# EasyEDA_Source.net
KiCad netlist of a schematic drawn in EasyEDA
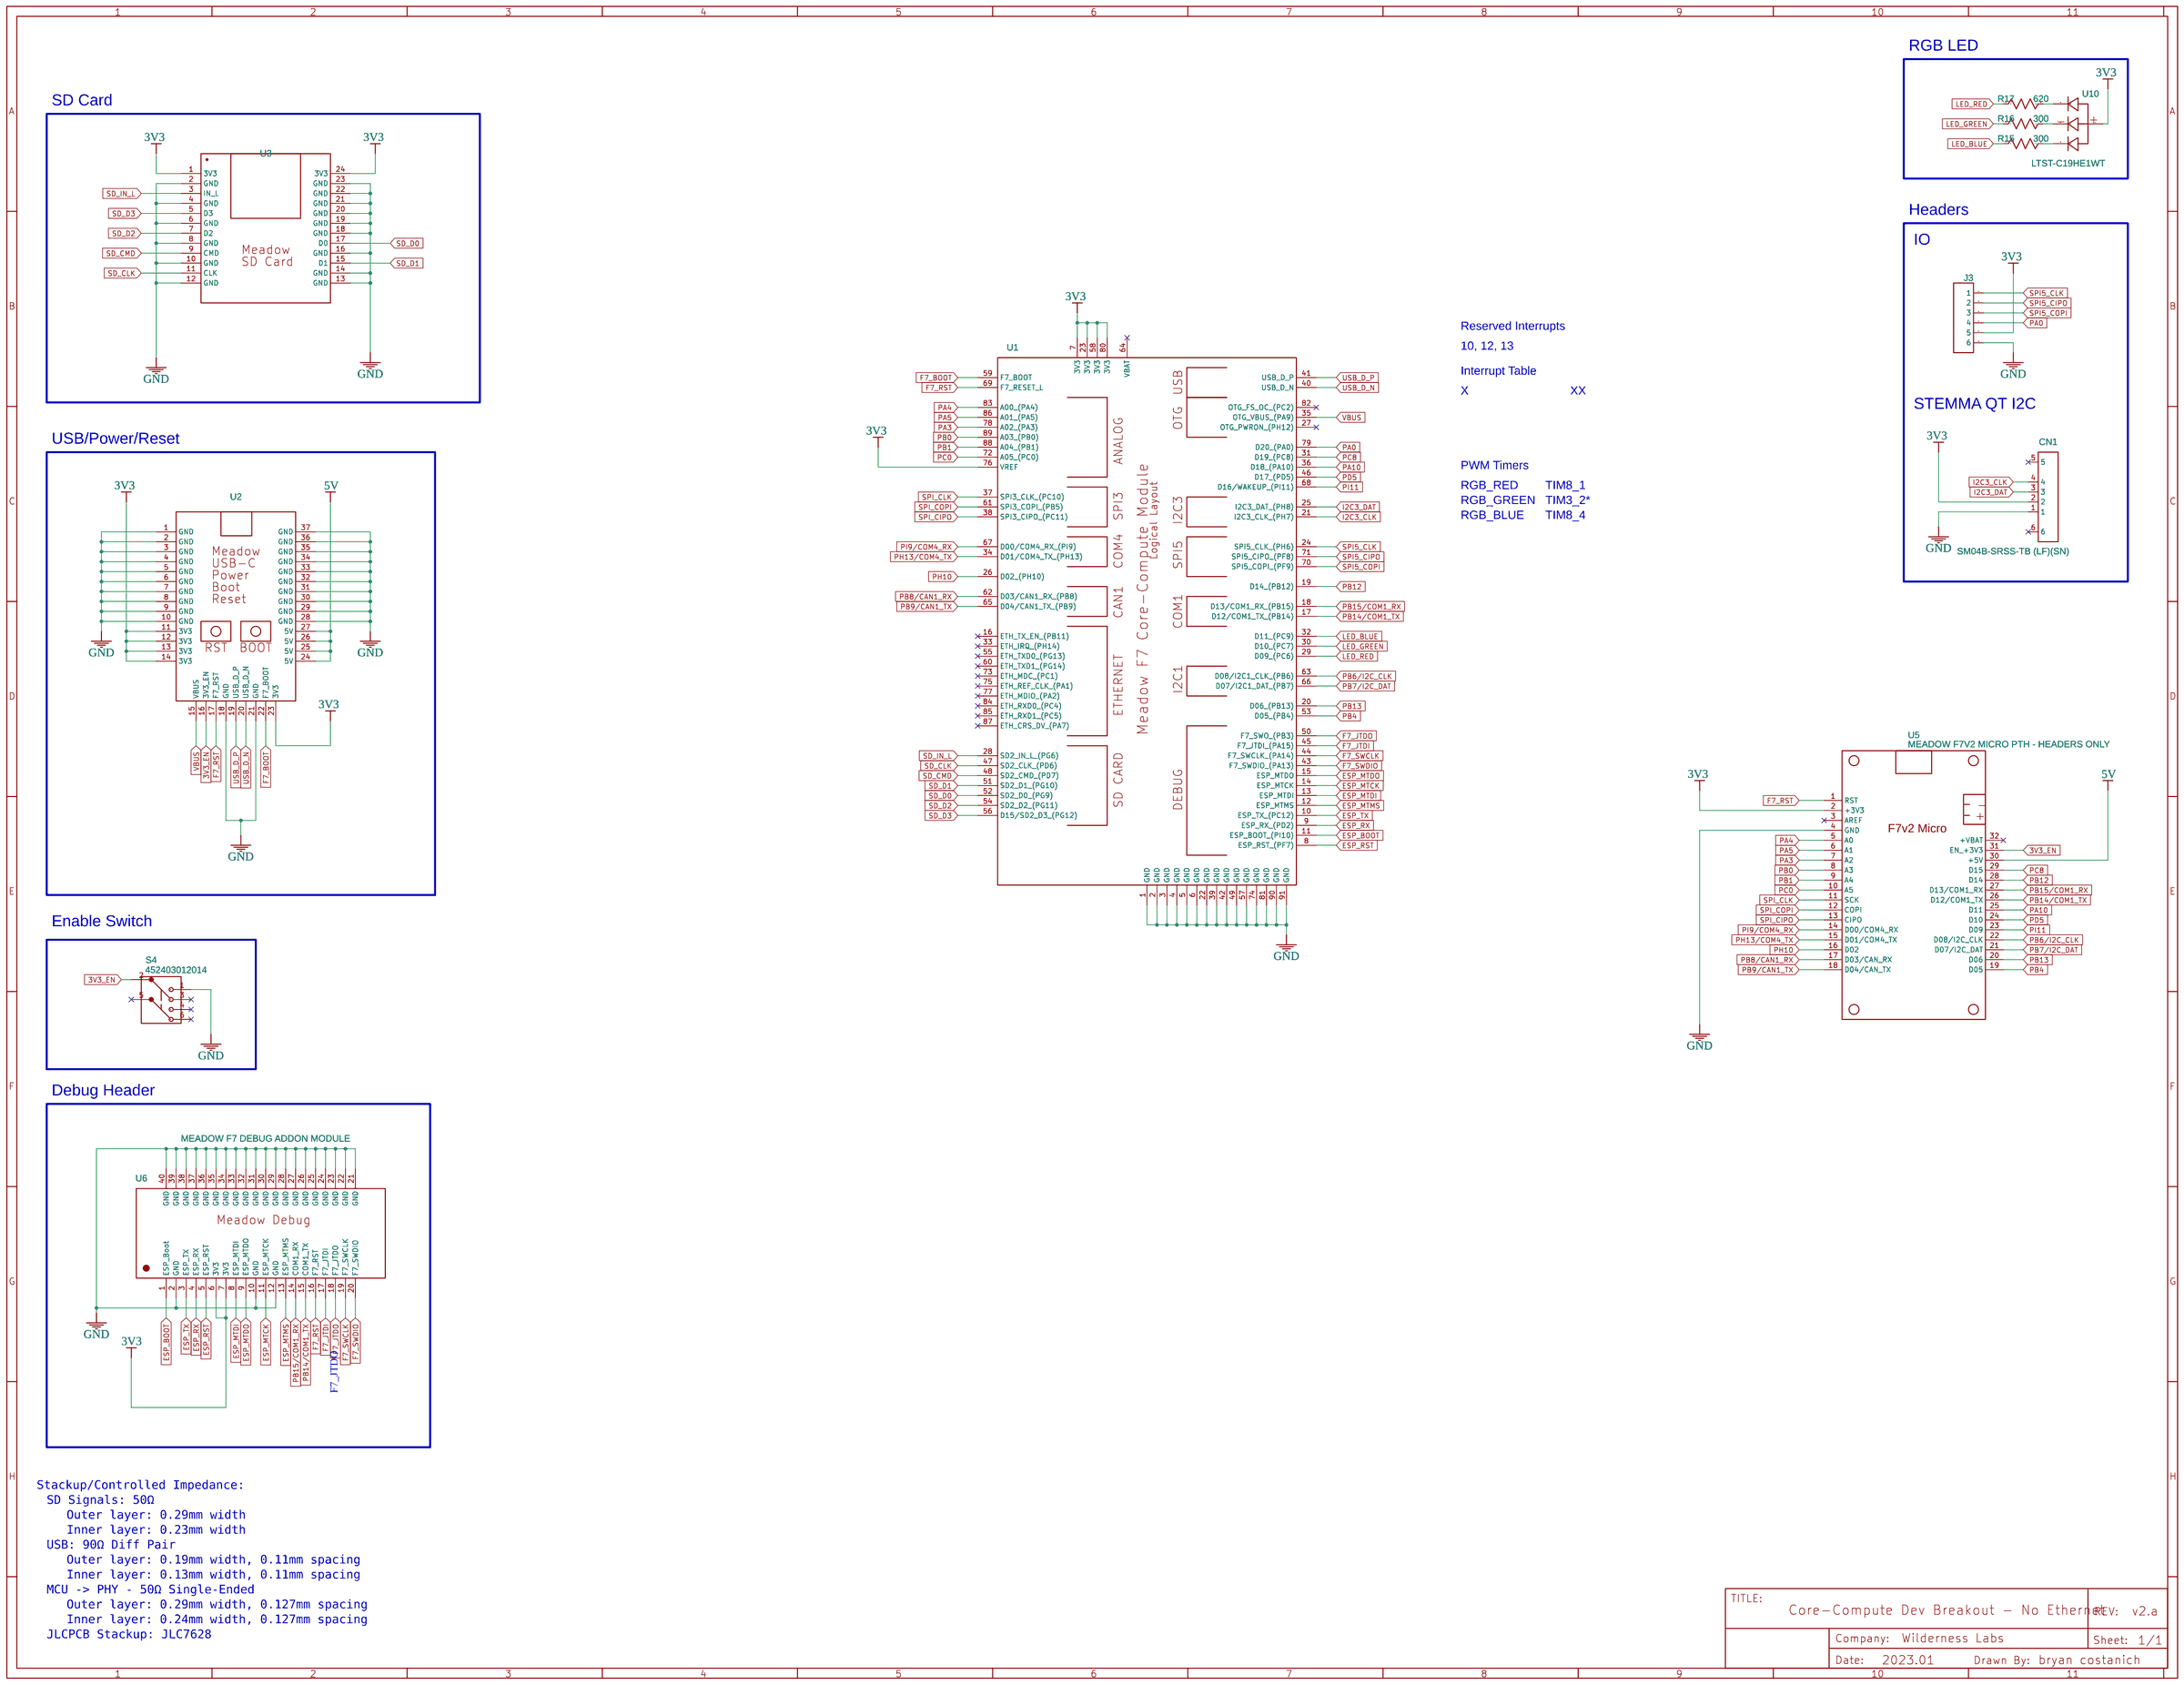
[diagram p0: schematic sheet]

(export (version "E")
  (design (tool "Eeschema 10.0.6"))
  (components
    (comp (ref "CN1")
      (value "SM04B-SRSS-TB (LF)(SN)")
      (fields (field (name "BOM_Supplier Part") "C160404"))
      (libsource (lib "") (part "SM04B-SRSS-TB (LF)(SN)"))
    )
    (comp (ref "J3")
      (value "HDR-M-2.54_1x6")
      (fields (field (name "BOM_Supplier Part") "C190819"))
      (libsource (lib "") (part "HDR-M-2.54_1x6"))
    )
    (comp (ref "R15")
      (value "300")
      (fields (field (name "BOM_Manufacturer Part") "RC0603FR-07300RL"))
      (libsource (lib "") (part "R_0603_US"))
    )
    (comp (ref "R16")
      (value "300")
      (fields (field (name "BOM_Manufacturer Part") "RC0603FR-07300RL"))
      (libsource (lib "") (part "R_0603_US"))
    )
    (comp (ref "R17")
      (value "620")
      (fields (field (name "BOM_Manufacturer Part") "RC0603FR-07620RL"))
      (libsource (lib "") (part "R_0603_US"))
    )
    (comp (ref "S4") (value "452403012014") (libsource (lib "") (part "452403012014")))
    (comp (ref "U1")
      (value "Meadow F7v2 Core-Compute Module - Logical")
      (libsource (lib "") (part "Meadow F7v2 Core-Compute Module - Logical"))
    )
    (comp (ref "U2")
      (value "Meadow Core-Compute USB-C, Power, Boot, and Reset Addon Module")
      (libsource (lib "") (part "Meadow Core-Compute USB-C, Power, Boot, and Reset Addon Module"))
    )
    (comp (ref "U3")
      (value "Meadow Core-Compute SD-Card Addon")
      (libsource (lib "") (part "Meadow Core-Compute SD-Card Addon"))
    )
    (comp (ref "U5")
      (value "MEADOW F7V2 MICRO PTH - HEADERS ONLY")
      (fields
        (field (name "BOM_Manufacturer Part") "MEDF7DEV")
        (field (name "BOM_Supplier Part") "977-MEADOWF7MICRO")
      )
      (libsource (lib "") (part "MEADOW F7V2 MICRO PTH - HEADERS ONLY"))
    )
    (comp (ref "U6")
      (value "MEADOW F7 DEBUG ADDON MODULE")
      (libsource (lib "") (part "MEADOW F7 DEBUG ADDON MODULE"))
    )
    (comp (ref "U10")
      (value "LTST-C19HE1WT")
      (fields
        (field (name "BOM_Manufacturer Part") "LTST-C19HE1WT-H")
        (field (name "BOM_Supplier Part") "C427425")
      )
      (libsource (lib "") (part "LTST-C19HE1WT-H"))
    )
  )
  (nets
    (net (code "1") (name "3V3") (class "Default")
      (node (ref "CN1") (pin "2") (pinfunction "2_2") (pintype "unspecified"))
      (node (ref "J3") (pin "5") (pinfunction "5_5") (pintype "input"))
      (node (ref "U1") (pin "23") (pinfunction "3V3_23") (pintype "unspecified"))
      (node (ref "U1") (pin "58") (pinfunction "3V3_58") (pintype "passive"))
      (node (ref "U1") (pin "7") (pinfunction "3V3_7") (pintype "unspecified"))
      (node (ref "U1") (pin "76") (pinfunction "VREF_76") (pintype "input"))
      (node (ref "U1") (pin "80") (pinfunction "3V3_80") (pintype "unspecified"))
      (node (ref "U10") (pin "4") (pinfunction "A_4") (pintype "unspecified"))
      (node (ref "U2") (pin "11") (pinfunction "3V3_11") (pintype "unspecified"))
      (node (ref "U2") (pin "12") (pinfunction "3V3_12") (pintype "unspecified"))
      (node (ref "U2") (pin "13") (pinfunction "3V3_13") (pintype "unspecified"))
      (node (ref "U2") (pin "14") (pinfunction "3V3_14") (pintype "unspecified"))
      (node (ref "U2") (pin "23") (pinfunction "3V3_23") (pintype "passive"))
      (node (ref "U3") (pin "1") (pinfunction "3V3_1") (pintype "unspecified"))
      (node (ref "U3") (pin "24") (pinfunction "3V3_24") (pintype "passive"))
      (node (ref "U5") (pin "2") (pinfunction "+3V3_2") (pintype "passive"))
      (node (ref "U6") (pin "6") (pinfunction "3V3_6") (pintype "unspecified"))
      (node (ref "U6") (pin "7") (pinfunction "3V3_7") (pintype "unspecified"))
    )
    (net (code "2") (name "3V3_EN") (class "Default")
      (node (ref "S4") (pin "2") (pinfunction "1_2") (pintype "unspecified"))
      (node (ref "U2") (pin "16") (pinfunction "3V3_EN_16") (pintype "unspecified"))
      (node (ref "U5") (pin "31") (pinfunction "EN_+3V3_31") (pintype "unspecified"))
    )
    (net (code "3") (name "5V") (class "Default")
      (node (ref "U2") (pin "24") (pinfunction "5V_24") (pintype "passive"))
      (node (ref "U2") (pin "25") (pinfunction "5V_25") (pintype "passive"))
      (node (ref "U2") (pin "26") (pinfunction "5V_26") (pintype "passive"))
      (node (ref "U2") (pin "27") (pinfunction "5V_27") (pintype "passive"))
      (node (ref "U5") (pin "30") (pinfunction "+5V_30") (pintype "passive"))
    )
    (net (code "4") (name "ESP_BOOT") (class "Default")
      (node (ref "U1") (pin "11") (pinfunction "ESP_BOOT_(PI10)_11") (pintype "unspecified"))
      (node (ref "U6") (pin "1") (pinfunction "ESP_Boot_1") (pintype "unspecified"))
    )
    (net (code "5") (name "ESP_MTCK") (class "Default")
      (node (ref "U1") (pin "14") (pinfunction "ESP_MTCK_14") (pintype "unspecified"))
      (node (ref "U6") (pin "11") (pinfunction "ESP_MTCK_11") (pintype "unspecified"))
    )
    (net (code "6") (name "ESP_MTDI") (class "Default")
      (node (ref "U1") (pin "13") (pinfunction "ESP_MTDI_13") (pintype "unspecified"))
      (node (ref "U6") (pin "8") (pinfunction "ESP_MTDI_8") (pintype "unspecified"))
    )
    (net (code "7") (name "ESP_MTDO") (class "Default")
      (node (ref "U1") (pin "15") (pinfunction "ESP_MTDO_15") (pintype "unspecified"))
      (node (ref "U6") (pin "9") (pinfunction "ESP_MTDO_9") (pintype "unspecified"))
    )
    (net (code "8") (name "ESP_MTMS") (class "Default")
      (node (ref "U1") (pin "12") (pinfunction "ESP_MTMS_12") (pintype "unspecified"))
      (node (ref "U6") (pin "13") (pinfunction "ESP_MTMS_13") (pintype "unspecified"))
    )
    (net (code "9") (name "ESP_RST") (class "Default")
      (node (ref "U1") (pin "8") (pinfunction "ESP_RST_(PF7)_8") (pintype "unspecified"))
      (node (ref "U6") (pin "5") (pinfunction "ESP_RST_5") (pintype "unspecified"))
    )
    (net (code "10") (name "ESP_RX") (class "Default")
      (node (ref "U1") (pin "9") (pinfunction "ESP_RX_(PD2)_9") (pintype "unspecified"))
      (node (ref "U6") (pin "4") (pinfunction "ESP_RX_4") (pintype "unspecified"))
    )
    (net (code "11") (name "ESP_TX") (class "Default")
      (node (ref "U1") (pin "10") (pinfunction "ESP_TX_(PC12)_10") (pintype "unspecified"))
      (node (ref "U6") (pin "3") (pinfunction "ESP_TX_3") (pintype "unspecified"))
    )
    (net (code "12") (name "F7_BOOT") (class "Default")
      (node (ref "U1") (pin "59") (pinfunction "F7_BOOT_59") (pintype "unspecified"))
      (node (ref "U2") (pin "22") (pinfunction "F7_BOOT_22") (pintype "unspecified"))
    )
    (net (code "13") (name "F7_JTDI") (class "Default")
      (node (ref "U1") (pin "45") (pinfunction "F7_JTDI_(PA15)_45") (pintype "unspecified"))
      (node (ref "U6") (pin "17") (pinfunction "F7_JTDI_17") (pintype "unspecified"))
    )
    (net (code "14") (name "F7_JTDO") (class "Default")
      (node (ref "U1") (pin "50") (pinfunction "F7_SWO_(PB3)_50") (pintype "unspecified"))
      (node (ref "U6") (pin "18") (pinfunction "F7_JTDO_18") (pintype "unspecified"))
    )
    (net (code "15") (name "F7_RST") (class "Default")
      (node (ref "U1") (pin "69") (pinfunction "F7_RESET_L_69") (pintype "unspecified"))
      (node (ref "U2") (pin "17") (pinfunction "F7_RST_17") (pintype "unspecified"))
      (node (ref "U5") (pin "1") (pinfunction "RST_1") (pintype "input"))
      (node (ref "U6") (pin "16") (pinfunction "F7_RST_16") (pintype "unspecified"))
    )
    (net (code "16") (name "F7_SWCLK") (class "Default")
      (node (ref "U1") (pin "44") (pinfunction "F7_SWCLK_(PA14)_44") (pintype "unspecified"))
      (node (ref "U6") (pin "19") (pinfunction "F7_SWCLK_19") (pintype "unspecified"))
    )
    (net (code "17") (name "F7_SWDIO") (class "Default")
      (node (ref "U1") (pin "43") (pinfunction "F7_SWDIO_(PA13)_43") (pintype "unspecified"))
      (node (ref "U6") (pin "20") (pinfunction "F7_SWDIO_20") (pintype "unspecified"))
    )
    (net (code "18") (name "GND") (class "Default")
      (node (ref "CN1") (pin "1") (pinfunction "1_1") (pintype "unspecified"))
      (node (ref "J3") (pin "6") (pinfunction "6_6") (pintype "input"))
      (node (ref "S4") (pin "1") (pinfunction "1_1") (pintype "unspecified"))
      (node (ref "U1") (pin "1") (pinfunction "GND_1") (pintype "passive"))
      (node (ref "U1") (pin "2") (pinfunction "GND_2") (pintype "passive"))
      (node (ref "U1") (pin "22") (pinfunction "GND_22") (pintype "passive"))
      (node (ref "U1") (pin "3") (pinfunction "GND_3") (pintype "passive"))
      (node (ref "U1") (pin "39") (pinfunction "GND_39") (pintype "passive"))
      (node (ref "U1") (pin "4") (pinfunction "GND_4") (pintype "passive"))
      (node (ref "U1") (pin "42") (pinfunction "GND_42") (pintype "passive"))
      (node (ref "U1") (pin "49") (pinfunction "GND_49") (pintype "passive"))
      (node (ref "U1") (pin "5") (pinfunction "GND_5") (pintype "passive"))
      (node (ref "U1") (pin "57") (pinfunction "GND_57") (pintype "passive"))
      (node (ref "U1") (pin "6") (pinfunction "GND_6") (pintype "passive"))
      (node (ref "U1") (pin "74") (pinfunction "GND_74") (pintype "passive"))
      (node (ref "U1") (pin "81") (pinfunction "GND_81") (pintype "passive"))
      (node (ref "U1") (pin "90") (pinfunction "GND_90") (pintype "passive"))
      (node (ref "U1") (pin "91") (pinfunction "GND_91") (pintype "passive"))
      (node (ref "U2") (pin "1") (pinfunction "GND_1") (pintype "unspecified"))
      (node (ref "U2") (pin "10") (pinfunction "GND_10") (pintype "unspecified"))
      (node (ref "U2") (pin "18") (pinfunction "GND_18") (pintype "unspecified"))
      (node (ref "U2") (pin "2") (pinfunction "GND_2") (pintype "unspecified"))
      (node (ref "U2") (pin "21") (pinfunction "GND_21") (pintype "unspecified"))
      (node (ref "U2") (pin "28") (pinfunction "GND_28") (pintype "unspecified"))
      (node (ref "U2") (pin "29") (pinfunction "GND_29") (pintype "unspecified"))
      (node (ref "U2") (pin "3") (pinfunction "GND_3") (pintype "unspecified"))
      (node (ref "U2") (pin "30") (pinfunction "GND_30") (pintype "unspecified"))
      (node (ref "U2") (pin "31") (pinfunction "GND_31") (pintype "unspecified"))
      (node (ref "U2") (pin "32") (pinfunction "GND_32") (pintype "unspecified"))
      (node (ref "U2") (pin "33") (pinfunction "GND_33") (pintype "unspecified"))
      (node (ref "U2") (pin "34") (pinfunction "GND_34") (pintype "unspecified"))
      (node (ref "U2") (pin "35") (pinfunction "GND_35") (pintype "unspecified"))
      (node (ref "U2") (pin "36") (pinfunction "GND_36") (pintype "unspecified"))
      (node (ref "U2") (pin "37") (pinfunction "GND_37") (pintype "unspecified"))
      (node (ref "U2") (pin "4") (pinfunction "GND_4") (pintype "unspecified"))
      (node (ref "U2") (pin "5") (pinfunction "GND_5") (pintype "unspecified"))
      (node (ref "U2") (pin "6") (pinfunction "GND_6") (pintype "unspecified"))
      (node (ref "U2") (pin "7") (pinfunction "GND_7") (pintype "unspecified"))
      (node (ref "U2") (pin "8") (pinfunction "GND_8") (pintype "unspecified"))
      (node (ref "U2") (pin "9") (pinfunction "GND_9") (pintype "unspecified"))
      (node (ref "U3") (pin "10") (pinfunction "GND_10") (pintype "unspecified"))
      (node (ref "U3") (pin "12") (pinfunction "GND_12") (pintype "unspecified"))
      (node (ref "U3") (pin "13") (pinfunction "GND_13") (pintype "unspecified"))
      (node (ref "U3") (pin "14") (pinfunction "GND_14") (pintype "unspecified"))
      (node (ref "U3") (pin "16") (pinfunction "GND_16") (pintype "passive"))
      (node (ref "U3") (pin "18") (pinfunction "GND_18") (pintype "passive"))
      (node (ref "U3") (pin "19") (pinfunction "GND_19") (pintype "passive"))
      (node (ref "U3") (pin "2") (pinfunction "GND_2") (pintype "unspecified"))
      (node (ref "U3") (pin "20") (pinfunction "GND_20") (pintype "passive"))
      (node (ref "U3") (pin "21") (pinfunction "GND_21") (pintype "passive"))
      (node (ref "U3") (pin "22") (pinfunction "GND_22") (pintype "passive"))
      (node (ref "U3") (pin "23") (pinfunction "GND_23") (pintype "passive"))
      (node (ref "U3") (pin "4") (pinfunction "GND_4") (pintype "unspecified"))
      (node (ref "U3") (pin "6") (pinfunction "GND_6") (pintype "unspecified"))
      (node (ref "U3") (pin "8") (pinfunction "GND_8") (pintype "unspecified"))
      (node (ref "U5") (pin "4") (pinfunction "GND_4") (pintype "passive"))
      (node (ref "U6") (pin "10") (pinfunction "GND_10") (pintype "unspecified"))
      (node (ref "U6") (pin "12") (pinfunction "GND_12") (pintype "unspecified"))
      (node (ref "U6") (pin "2") (pinfunction "GND_2") (pintype "unspecified"))
      (node (ref "U6") (pin "21") (pinfunction "GND_21") (pintype "unspecified"))
      (node (ref "U6") (pin "22") (pinfunction "GND_22") (pintype "unspecified"))
      (node (ref "U6") (pin "23") (pinfunction "GND_23") (pintype "unspecified"))
      (node (ref "U6") (pin "24") (pinfunction "GND_24") (pintype "unspecified"))
      (node (ref "U6") (pin "25") (pinfunction "GND_25") (pintype "unspecified"))
      (node (ref "U6") (pin "26") (pinfunction "GND_26") (pintype "unspecified"))
      (node (ref "U6") (pin "27") (pinfunction "GND_27") (pintype "unspecified"))
      (node (ref "U6") (pin "28") (pinfunction "GND_28") (pintype "unspecified"))
      (node (ref "U6") (pin "29") (pinfunction "GND_29") (pintype "unspecified"))
      (node (ref "U6") (pin "30") (pinfunction "GND_30") (pintype "unspecified"))
      (node (ref "U6") (pin "31") (pinfunction "GND_31") (pintype "unspecified"))
      (node (ref "U6") (pin "32") (pinfunction "GND_32") (pintype "unspecified"))
      (node (ref "U6") (pin "33") (pinfunction "GND_33") (pintype "unspecified"))
      (node (ref "U6") (pin "34") (pinfunction "GND_34") (pintype "unspecified"))
      (node (ref "U6") (pin "35") (pinfunction "GND_35") (pintype "unspecified"))
      (node (ref "U6") (pin "36") (pinfunction "GND_36") (pintype "unspecified"))
      (node (ref "U6") (pin "37") (pinfunction "GND_37") (pintype "unspecified"))
      (node (ref "U6") (pin "38") (pinfunction "GND_38") (pintype "unspecified"))
      (node (ref "U6") (pin "39") (pinfunction "GND_39") (pintype "unspecified"))
      (node (ref "U6") (pin "40") (pinfunction "GND_40") (pintype "unspecified"))
    )
    (net (code "19") (name "I2C3_CLK") (class "Default")
      (node (ref "CN1") (pin "4") (pinfunction "4_4") (pintype "unspecified"))
      (node (ref "U1") (pin "21") (pinfunction "I2C3_CLK_(PH7)_21") (pintype "unspecified"))
    )
    (net (code "20") (name "I2C3_DAT") (class "Default")
      (node (ref "CN1") (pin "3") (pinfunction "3_3") (pintype "unspecified"))
      (node (ref "U1") (pin "25") (pinfunction "I2C3_DAT_(PH8)_25") (pintype "unspecified"))
    )
    (net (code "21") (name "LED_BLUE") (class "Default")
      (node (ref "R15") (pin "1") (pinfunction "1_1") (pintype "unspecified"))
      (node (ref "U1") (pin "32") (pinfunction "D11_(PC9)_32") (pintype "unspecified"))
    )
    (net (code "22") (name "LED_GREEN") (class "Default")
      (node (ref "R16") (pin "1") (pinfunction "1_1") (pintype "unspecified"))
      (node (ref "U1") (pin "30") (pinfunction "D10_(PC7)_30") (pintype "unspecified"))
    )
    (net (code "23") (name "LED_RED") (class "Default")
      (node (ref "R17") (pin "1") (pinfunction "1_1") (pintype "unspecified"))
      (node (ref "U1") (pin "29") (pinfunction "D09_(PC6)_29") (pintype "unspecified"))
    )
    (net (code "24") (name "Net-(U10-C1)") (class "Default")
      (node (ref "R17") (pin "2") (pinfunction "2_2") (pintype "unspecified"))
      (node (ref "U10") (pin "1") (pinfunction "C1_1") (pintype "unspecified"))
    )
    (net (code "25") (name "Net-(U10-C2)") (class "Default")
      (node (ref "R16") (pin "2") (pinfunction "2_2") (pintype "unspecified"))
      (node (ref "U10") (pin "2") (pinfunction "C2_2") (pintype "unspecified"))
    )
    (net (code "26") (name "Net-(U10-C3)") (class "Default")
      (node (ref "R15") (pin "2") (pinfunction "2_2") (pintype "unspecified"))
      (node (ref "U10") (pin "3") (pinfunction "C3_3") (pintype "unspecified"))
    )
    (net (code "27") (name "PA0") (class "Default")
      (node (ref "J3") (pin "4") (pinfunction "4_4") (pintype "input"))
      (node (ref "U1") (pin "79") (pinfunction "D20_(PA0)_79") (pintype "unspecified"))
    )
    (net (code "28") (name "PA3") (class "Default")
      (node (ref "U1") (pin "78") (pinfunction "A02_(PA3)_78") (pintype "unspecified"))
      (node (ref "U5") (pin "7") (pinfunction "A2_7") (pintype "bidirectional"))
    )
    (net (code "29") (name "PA4") (class "Default")
      (node (ref "U1") (pin "83") (pinfunction "A00_(PA4)_83") (pintype "unspecified"))
      (node (ref "U5") (pin "5") (pinfunction "A0_5") (pintype "bidirectional"))
    )
    (net (code "30") (name "PA5") (class "Default")
      (node (ref "U1") (pin "86") (pinfunction "A01_(PA5)_86") (pintype "unspecified"))
      (node (ref "U5") (pin "6") (pinfunction "A1_6") (pintype "bidirectional"))
    )
    (net (code "31") (name "PA10") (class "Default")
      (node (ref "U1") (pin "36") (pinfunction "D18_(PA10)_36") (pintype "unspecified"))
      (node (ref "U5") (pin "25") (pinfunction "D11_25") (pintype "bidirectional"))
    )
    (net (code "32") (name "PB0") (class "Default")
      (node (ref "U1") (pin "89") (pinfunction "A03_(PB0)_89") (pintype "unspecified"))
      (node (ref "U5") (pin "8") (pinfunction "A3_8") (pintype "bidirectional"))
    )
    (net (code "33") (name "PB1") (class "Default")
      (node (ref "U1") (pin "88") (pinfunction "A04_(PB1)_88") (pintype "unspecified"))
      (node (ref "U5") (pin "9") (pinfunction "A4_9") (pintype "bidirectional"))
    )
    (net (code "34") (name "PB4") (class "Default")
      (node (ref "U1") (pin "53") (pinfunction "D05_(PB4)_53") (pintype "unspecified"))
      (node (ref "U5") (pin "19") (pinfunction "D05_19") (pintype "bidirectional"))
    )
    (net (code "35") (name "PB6{slash}I2C_CLK") (class "Default")
      (node (ref "U1") (pin "63") (pinfunction "D08/I2C1_CLK_(PB6)_63") (pintype "unspecified"))
      (node (ref "U5") (pin "22") (pinfunction "D08/I2C_CLK_22") (pintype "bidirectional"))
    )
    (net (code "36") (name "PB7{slash}I2C_DAT") (class "Default")
      (node (ref "U1") (pin "66") (pinfunction "D07/I2C1_DAT_(PB7)_66") (pintype "unspecified"))
      (node (ref "U5") (pin "21") (pinfunction "D07/I2C_DAT_21") (pintype "bidirectional"))
    )
    (net (code "37") (name "PB8{slash}CAN1_RX") (class "Default")
      (node (ref "U1") (pin "62") (pinfunction "D03/CAN1_RX_(PB8)_62") (pintype "unspecified"))
      (node (ref "U5") (pin "17") (pinfunction "D03/CAN_RX_17") (pintype "bidirectional"))
    )
    (net (code "38") (name "PB9{slash}CAN1_TX") (class "Default")
      (node (ref "U1") (pin "65") (pinfunction "D04/CAN1_TX_(PB9)_65") (pintype "unspecified"))
      (node (ref "U5") (pin "18") (pinfunction "D04/CAN_TX_18") (pintype "bidirectional"))
    )
    (net (code "39") (name "PB12") (class "Default")
      (node (ref "U1") (pin "19") (pinfunction "D14_(PB12)_19") (pintype "unspecified"))
      (node (ref "U5") (pin "28") (pinfunction "D14_28") (pintype "bidirectional"))
    )
    (net (code "40") (name "PB13") (class "Default")
      (node (ref "U1") (pin "20") (pinfunction "D06_(PB13)_20") (pintype "unspecified"))
      (node (ref "U5") (pin "20") (pinfunction "D06_20") (pintype "bidirectional"))
    )
    (net (code "41") (name "PB14{slash}COM1_TX") (class "Default")
      (node (ref "U1") (pin "17") (pinfunction "D12/COM1_TX_(PB14)_17") (pintype "unspecified"))
      (node (ref "U5") (pin "26") (pinfunction "D12/COM1_TX_26") (pintype "bidirectional"))
      (node (ref "U6") (pin "15") (pinfunction "COM1_TX_15") (pintype "unspecified"))
    )
    (net (code "42") (name "PB15{slash}COM1_RX") (class "Default")
      (node (ref "U1") (pin "18") (pinfunction "D13/COM1_RX_(PB15)_18") (pintype "unspecified"))
      (node (ref "U5") (pin "27") (pinfunction "D13/COM1_RX_27") (pintype "bidirectional"))
      (node (ref "U6") (pin "14") (pinfunction "COM1_RX_14") (pintype "unspecified"))
    )
    (net (code "43") (name "PC0") (class "Default")
      (node (ref "U1") (pin "72") (pinfunction "A05_(PC0)_72") (pintype "unspecified"))
      (node (ref "U5") (pin "10") (pinfunction "A5_10") (pintype "bidirectional"))
    )
    (net (code "44") (name "PC8") (class "Default")
      (node (ref "U1") (pin "31") (pinfunction "D19_(PC8)_31") (pintype "unspecified"))
      (node (ref "U5") (pin "29") (pinfunction "D15_29") (pintype "bidirectional"))
    )
    (net (code "45") (name "PD5") (class "Default")
      (node (ref "U1") (pin "46") (pinfunction "D17_(PD5)_46") (pintype "unspecified"))
      (node (ref "U5") (pin "24") (pinfunction "D10_24") (pintype "bidirectional"))
    )
    (net (code "46") (name "PH10") (class "Default")
      (node (ref "U1") (pin "26") (pinfunction "D02_(PH10)_26") (pintype "unspecified"))
      (node (ref "U5") (pin "16") (pinfunction "D02_16") (pintype "bidirectional"))
    )
    (net (code "47") (name "PH13{slash}COM4_TX") (class "Default")
      (node (ref "U1") (pin "34") (pinfunction "D01/COM4_TX_(PH13)_34") (pintype "unspecified"))
      (node (ref "U5") (pin "15") (pinfunction "D01/COM4_TX_15") (pintype "bidirectional"))
    )
    (net (code "48") (name "PI9{slash}COM4_RX") (class "Default")
      (node (ref "U1") (pin "67") (pinfunction "D00/COM4_RX_(PI9)_67") (pintype "unspecified"))
      (node (ref "U5") (pin "14") (pinfunction "D00/COM4_RX_14") (pintype "bidirectional"))
    )
    (net (code "49") (name "PI11") (class "Default")
      (node (ref "U1") (pin "68") (pinfunction "D16/WAKEUP_(PI11)_68") (pintype "unspecified"))
      (node (ref "U5") (pin "23") (pinfunction "D09_23") (pintype "bidirectional"))
    )
    (net (code "50") (name "SD_CLK") (class "Default")
      (node (ref "U1") (pin "47") (pinfunction "SD2_CLK_(PD6)_47") (pintype "unspecified"))
      (node (ref "U3") (pin "11") (pinfunction "CLK_11") (pintype "unspecified"))
    )
    (net (code "51") (name "SD_CMD") (class "Default")
      (node (ref "U1") (pin "48") (pinfunction "SD2_CMD_(PD7)_48") (pintype "unspecified"))
      (node (ref "U3") (pin "9") (pinfunction "CMD_9") (pintype "unspecified"))
    )
    (net (code "52") (name "SD_D0") (class "Default")
      (node (ref "U1") (pin "52") (pinfunction "SD2_D0_(PG9)_52") (pintype "unspecified"))
      (node (ref "U3") (pin "17") (pinfunction "D0_17") (pintype "passive"))
    )
    (net (code "53") (name "SD_D1") (class "Default")
      (node (ref "U1") (pin "51") (pinfunction "SD2_D1_(PG10)_51") (pintype "unspecified"))
      (node (ref "U3") (pin "15") (pinfunction "D1_15") (pintype "unspecified"))
    )
    (net (code "54") (name "SD_D2") (class "Default")
      (node (ref "U1") (pin "54") (pinfunction "SD2_D2_(PG11)_54") (pintype "unspecified"))
      (node (ref "U3") (pin "7") (pinfunction "D2_7") (pintype "unspecified"))
    )
    (net (code "55") (name "SD_D3") (class "Default")
      (node (ref "U1") (pin "56") (pinfunction "D15/SD2_D3_(PG12)_56") (pintype "unspecified"))
      (node (ref "U3") (pin "5") (pinfunction "D3_5") (pintype "unspecified"))
    )
    (net (code "56") (name "SD_IN_L") (class "Default")
      (node (ref "U1") (pin "28") (pinfunction "SD2_IN_L_(PG6)_28") (pintype "unspecified"))
      (node (ref "U3") (pin "3") (pinfunction "IN_L_3") (pintype "unspecified"))
    )
    (net (code "57") (name "SPI5_CIPO") (class "Default")
      (node (ref "J3") (pin "2") (pinfunction "2_2") (pintype "input"))
      (node (ref "U1") (pin "71") (pinfunction "SPI5_CIPO_(PF8)_71") (pintype "unspecified"))
    )
    (net (code "58") (name "SPI5_CLK") (class "Default")
      (node (ref "J3") (pin "1") (pinfunction "1_1") (pintype "input"))
      (node (ref "U1") (pin "24") (pinfunction "SPI5_CLK_(PH6)_24") (pintype "unspecified"))
    )
    (net (code "59") (name "SPI5_COPI") (class "Default")
      (node (ref "J3") (pin "3") (pinfunction "3_3") (pintype "input"))
      (node (ref "U1") (pin "70") (pinfunction "SPI5_COPI_(PF9)_70") (pintype "unspecified"))
    )
    (net (code "60") (name "SPI_CIPO") (class "Default")
      (node (ref "U1") (pin "38") (pinfunction "SPI3_CIPO_(PC11)_38") (pintype "unspecified"))
      (node (ref "U5") (pin "13") (pinfunction "CIPO_13") (pintype "bidirectional"))
    )
    (net (code "61") (name "SPI_CLK") (class "Default")
      (node (ref "U1") (pin "37") (pinfunction "SPI3_CLK_(PC10)_37") (pintype "unspecified"))
      (node (ref "U5") (pin "11") (pinfunction "SCK_11") (pintype "bidirectional"))
    )
    (net (code "62") (name "SPI_COPI") (class "Default")
      (node (ref "U1") (pin "61") (pinfunction "SPI3_COPI_(PB5)_61") (pintype "unspecified"))
      (node (ref "U5") (pin "12") (pinfunction "COPI_12") (pintype "bidirectional"))
    )
    (net (code "63") (name "USB_D_N") (class "Default")
      (node (ref "U1") (pin "40") (pinfunction "USB_D_N_40") (pintype "unspecified"))
      (node (ref "U2") (pin "20") (pinfunction "USB_D_N_20") (pintype "unspecified"))
    )
    (net (code "64") (name "USB_D_P") (class "Default")
      (node (ref "U1") (pin "41") (pinfunction "USB_D_P_41") (pintype "unspecified"))
      (node (ref "U2") (pin "19") (pinfunction "USB_D_P_19") (pintype "unspecified"))
    )
    (net (code "65") (name "VBUS") (class "Default")
      (node (ref "U1") (pin "35") (pinfunction "OTG_VBUS_(PA9)_35") (pintype "unspecified"))
      (node (ref "U2") (pin "15") (pinfunction "VBUS_15") (pintype "unspecified"))
    )
    (net (code "66") (name "unconnected-(CN1-Pad5)") (class "Default")
      (node (ref "CN1") (pin "5") (pinfunction "5_5") (pintype "unspecified+no_connect"))
    )
    (net (code "67") (name "unconnected-(CN1-Pad6)") (class "Default")
      (node (ref "CN1") (pin "6") (pinfunction "6_6") (pintype "unspecified+no_connect"))
    )
    (net (code "68") (name "unconnected-(S4-1-Pad3)") (class "Default")
      (node (ref "S4") (pin "3") (pinfunction "1_3") (pintype "unspecified+no_connect"))
    )
    (net (code "69") (name "unconnected-(S4-1-Pad4)") (class "Default")
      (node (ref "S4") (pin "4") (pinfunction "1_4") (pintype "unspecified+no_connect"))
    )
    (net (code "70") (name "unconnected-(S4-1-Pad6)") (class "Default")
      (node (ref "S4") (pin "6") (pinfunction "1_6") (pintype "unspecified+no_connect"))
    )
    (net (code "71") (name "unconnected-(S4-2-Pad5)") (class "Default")
      (node (ref "S4") (pin "5") (pinfunction "2_5") (pintype "unspecified+no_connect"))
    )
    (net (code "72") (name "unconnected-(U1-ETH_CRS_DV_(PA7)-Pad87)") (class "Default")
      (node (ref "U1") (pin "87") (pinfunction "ETH_CRS_DV_(PA7)_87") (pintype "unspecified+no_connect"))
    )
    (net (code "73") (name "unconnected-(U1-ETH_IRQ_(PH14)-Pad33)") (class "Default")
      (node (ref "U1") (pin "33") (pinfunction "ETH_IRQ_(PH14)_33") (pintype "unspecified+no_connect"))
    )
    (net (code "74") (name "unconnected-(U1-ETH_MDC_(PC1)-Pad73)") (class "Default")
      (node (ref "U1") (pin "73") (pinfunction "ETH_MDC_(PC1)_73") (pintype "unspecified+no_connect"))
    )
    (net (code "75") (name "unconnected-(U1-ETH_MDIO_(PA2)-Pad77)") (class "Default")
      (node (ref "U1") (pin "77") (pinfunction "ETH_MDIO_(PA2)_77") (pintype "unspecified+no_connect"))
    )
    (net (code "76") (name "unconnected-(U1-ETH_REF_CLK_(PA1)-Pad75)") (class "Default")
      (node (ref "U1") (pin "75") (pinfunction "ETH_REF_CLK_(PA1)_75") (pintype "unspecified+no_connect"))
    )
    (net (code "77") (name "unconnected-(U1-ETH_RXD0_(PC4)-Pad84)") (class "Default")
      (node (ref "U1") (pin "84") (pinfunction "ETH_RXD0_(PC4)_84") (pintype "unspecified+no_connect"))
    )
    (net (code "78") (name "unconnected-(U1-ETH_RXD1_(PC5)-Pad85)") (class "Default")
      (node (ref "U1") (pin "85") (pinfunction "ETH_RXD1_(PC5)_85") (pintype "unspecified+no_connect"))
    )
    (net (code "79") (name "unconnected-(U1-ETH_TXD0_(PG13)-Pad55)") (class "Default")
      (node (ref "U1") (pin "55") (pinfunction "ETH_TXD0_(PG13)_55") (pintype "unspecified+no_connect"))
    )
    (net (code "80") (name "unconnected-(U1-ETH_TXD1_(PG14)-Pad60)") (class "Default")
      (node (ref "U1") (pin "60") (pinfunction "ETH_TXD1_(PG14)_60") (pintype "unspecified+no_connect"))
    )
    (net (code "81") (name "unconnected-(U1-ETH_TX_EN_(PB11)-Pad16)") (class "Default")
      (node (ref "U1") (pin "16") (pinfunction "ETH_TX_EN_(PB11)_16") (pintype "unspecified+no_connect"))
    )
    (net (code "82") (name "unconnected-(U1-OTG_FS_OC_(PC2)-Pad82)") (class "Default")
      (node (ref "U1") (pin "82") (pinfunction "OTG_FS_OC_(PC2)_82") (pintype "unspecified+no_connect"))
    )
    (net (code "83") (name "unconnected-(U1-OTG_PWRON_(PH12)-Pad27)") (class "Default")
      (node (ref "U1") (pin "27") (pinfunction "OTG_PWRON_(PH12)_27") (pintype "unspecified+no_connect"))
    )
    (net (code "84") (name "unconnected-(U1-VBAT-Pad64)") (class "Default")
      (node (ref "U1") (pin "64") (pinfunction "VBAT_64") (pintype "input+no_connect"))
    )
    (net (code "85") (name "unconnected-(U5-+VBAT-Pad32)") (class "Default")
      (node (ref "U5") (pin "32") (pinfunction "+VBAT_32") (pintype "passive+no_connect"))
    )
    (net (code "86") (name "unconnected-(U5-AREF-Pad3)") (class "Default")
      (node (ref "U5") (pin "3") (pinfunction "AREF_3") (pintype "input+no_connect"))
    )
  )
)
